# combo_-_no_usb_-_pth.net
KiCad netlist of a schematic drawn in EAGLE
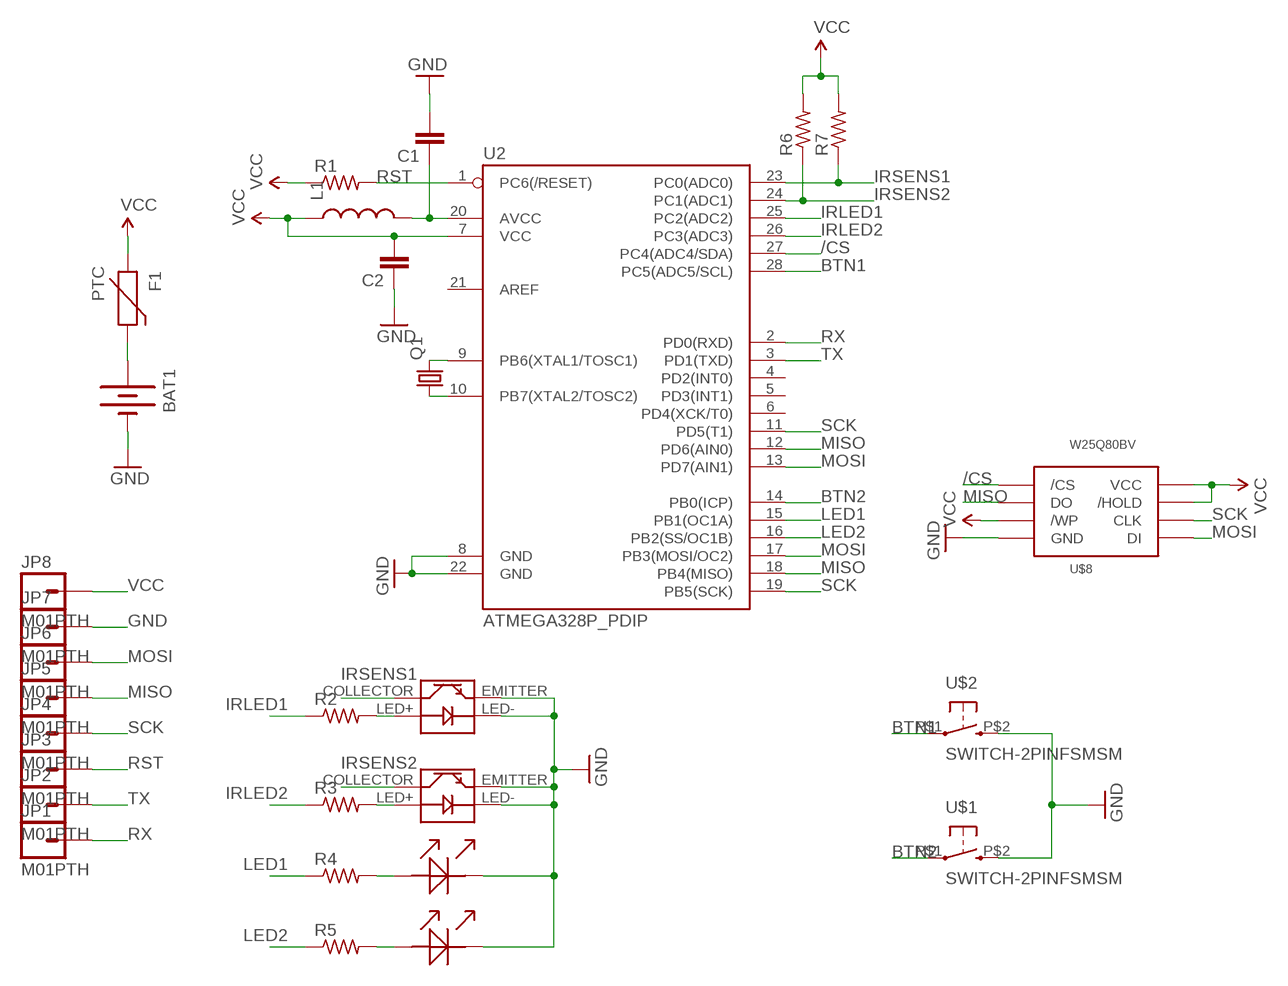
[diagram p0: schematic, sheet 1]

(export (version "E")
  (design (tool "Eeschema 10.0.6"))
  (components
    (comp (ref "BAT1")
      (value "BATTERYBA2032SM")
      (footprint "eagle-import:BA2032SM")
      (libsource (lib "eagle-import") (part "BATTERYBA2032SM"))
    )
    (comp (ref "C1")
      (value "CAP0805")
      (footprint "eagle-import:0805")
      (libsource (lib "eagle-import") (part "CAP0805"))
    )
    (comp (ref "C2")
      (value "CAP0805")
      (footprint "eagle-import:0805")
      (libsource (lib "eagle-import") (part "CAP0805"))
    )
    (comp (ref "F1")
      (value "PTC")
      (footprint "eagle-import:R0805")
      (libsource (lib "eagle-import") (part "PTC"))
    )
    (comp (ref "JP1")
      (value "M01PTH")
      (footprint "eagle-import:1X01")
      (libsource (lib "eagle-import") (part "M01PTH"))
    )
    (comp (ref "JP2")
      (value "M01PTH")
      (footprint "eagle-import:1X01")
      (libsource (lib "eagle-import") (part "M01PTH"))
    )
    (comp (ref "JP3")
      (value "M01PTH")
      (footprint "eagle-import:1X01")
      (libsource (lib "eagle-import") (part "M01PTH"))
    )
    (comp (ref "JP4")
      (value "M01PTH")
      (footprint "eagle-import:1X01")
      (libsource (lib "eagle-import") (part "M01PTH"))
    )
    (comp (ref "JP5")
      (value "M01PTH")
      (footprint "eagle-import:1X01")
      (libsource (lib "eagle-import") (part "M01PTH"))
    )
    (comp (ref "JP6")
      (value "M01PTH")
      (footprint "eagle-import:1X01")
      (libsource (lib "eagle-import") (part "M01PTH"))
    )
    (comp (ref "JP7")
      (value "M01PTH")
      (footprint "eagle-import:1X01")
      (libsource (lib "eagle-import") (part "M01PTH"))
    )
    (comp (ref "JP8")
      (value "M01PTH")
      (footprint "eagle-import:1X01")
      (libsource (lib "eagle-import") (part "M01PTH"))
    )
    (comp (ref "L1")
      (value "INDUCTOR0805")
      (footprint "eagle-import:0805")
      (libsource (lib "eagle-import") (part "INDUCTOR0805"))
    )
    (comp (ref "Q1")
      (value "CRYSTALTC26V")
      (footprint "eagle-import:TC26V")
      (libsource (lib "eagle-import") (part "CRYSTALTC26V"))
    )
    (comp (ref "R1")
      (value "R-US_M0805")
      (footprint "eagle-import:M0805")
      (libsource (lib "eagle-import") (part "R-US_M0805"))
    )
    (comp (ref "R2")
      (value "R-US_M0805")
      (footprint "eagle-import:M0805")
      (libsource (lib "eagle-import") (part "R-US_M0805"))
    )
    (comp (ref "R3")
      (value "R-US_M0805")
      (footprint "eagle-import:M0805")
      (libsource (lib "eagle-import") (part "R-US_M0805"))
    )
    (comp (ref "R4")
      (value "R-US_M0805")
      (footprint "eagle-import:M0805")
      (libsource (lib "eagle-import") (part "R-US_M0805"))
    )
    (comp (ref "R5")
      (value "R-US_M0805")
      (footprint "eagle-import:M0805")
      (libsource (lib "eagle-import") (part "R-US_M0805"))
    )
    (comp (ref "R6")
      (value "R-US_M0805")
      (footprint "eagle-import:M0805")
      (libsource (lib "eagle-import") (part "R-US_M0805"))
    )
    (comp (ref "R7")
      (value "R-US_M0805")
      (footprint "eagle-import:M0805")
      (libsource (lib "eagle-import") (part "R-US_M0805"))
    )
    (comp (ref "U$1")
      (value "SWITCH-2PINFSMSM")
      (footprint "eagle-import:FSMSM-BUTTON")
      (libsource (lib "eagle-import") (part "SWITCH-2PINFSMSM"))
    )
    (comp (ref "U$2")
      (value "SWITCH-2PINFSMSM")
      (footprint "eagle-import:FSMSM-BUTTON")
      (libsource (lib "eagle-import") (part "SWITCH-2PINFSMSM"))
    )
    (comp (ref "U$3")
      (value "IR_SENSORQRE1113")
      (footprint "eagle-import:QRE1113")
      (libsource (lib "eagle-import") (part "IR_SENSORQRE1113"))
    )
    (comp (ref "U$4")
      (value "IR_SENSORQRE1113")
      (footprint "eagle-import:QRE1113")
      (libsource (lib "eagle-import") (part "IR_SENSORQRE1113"))
    )
    (comp (ref "U$5")
      (value "LED0603")
      (footprint "eagle-import:0603")
      (libsource (lib "eagle-import") (part "LED0603"))
    )
    (comp (ref "U$6")
      (value "LED0603")
      (footprint "eagle-import:0603")
      (libsource (lib "eagle-import") (part "LED0603"))
    )
    (comp (ref "U$8")
      (value "W25Q80BVSOIC-08")
      (footprint "eagle-import:W25Q80BV-SOIC-208MIL")
      (libsource (lib "eagle-import") (part "W25Q80BVSOIC-08"))
    )
    (comp (ref "U2")
      (value "ATMEGA328P_PDIP")
      (footprint "eagle-import:DIL28-3")
      (libsource (lib "eagle-import") (part "ATMEGA328P_PDIP"))
    )
  )
  (nets
    (net (code "1") (name "/BTN1") (class "Default")
      (node (ref "U$2") (pin "P$1") (pinfunction "1_P$1") (pintype "passive"))
      (node (ref "U2") (pin "28") (pinfunction "PC5(ADC5/SCL)_28") (pintype "bidirectional"))
    )
    (net (code "2") (name "/BTN2") (class "Default")
      (node (ref "U$1") (pin "P$1") (pinfunction "1_P$1") (pintype "passive"))
      (node (ref "U2") (pin "14") (pinfunction "PB0(ICP)_14") (pintype "bidirectional"))
    )
    (net (code "3") (name "/IRLED1") (class "Default")
      (node (ref "R2") (pin "1") (pinfunction "1_1") (pintype "passive"))
      (node (ref "U2") (pin "25") (pinfunction "PC2(ADC2)_25") (pintype "bidirectional"))
    )
    (net (code "4") (name "/IRLED2") (class "Default")
      (node (ref "R3") (pin "1") (pinfunction "1_1") (pintype "passive"))
      (node (ref "U2") (pin "26") (pinfunction "PC3(ADC3)_26") (pintype "bidirectional"))
    )
    (net (code "5") (name "/IRSENS1") (class "Default")
      (node (ref "R7") (pin "1") (pinfunction "1_1") (pintype "passive"))
      (node (ref "U$3") (pin "COLLECTOR") (pinfunction "COLLECTOR_COLLECTOR") (pintype "input"))
      (node (ref "U2") (pin "23") (pinfunction "PC0(ADC0)_23") (pintype "bidirectional"))
    )
    (net (code "6") (name "/IRSENS2") (class "Default")
      (node (ref "R6") (pin "1") (pinfunction "1_1") (pintype "passive"))
      (node (ref "U$4") (pin "COLLECTOR") (pinfunction "COLLECTOR_COLLECTOR") (pintype "input"))
      (node (ref "U2") (pin "24") (pinfunction "PC1(ADC1)_24") (pintype "bidirectional"))
    )
    (net (code "7") (name "/LED1") (class "Default")
      (node (ref "R4") (pin "1") (pinfunction "1_1") (pintype "passive"))
      (node (ref "U2") (pin "15") (pinfunction "PB1(OC1A)_15") (pintype "bidirectional"))
    )
    (net (code "8") (name "/LED2") (class "Default")
      (node (ref "R5") (pin "1") (pinfunction "1_1") (pintype "passive"))
      (node (ref "U2") (pin "16") (pinfunction "PB2(SS/OC1B)_16") (pintype "bidirectional"))
    )
    (net (code "9") (name "/MISO") (class "Default")
      (node (ref "JP5") (pin "1") (pinfunction "1_1") (pintype "passive"))
      (node (ref "U$8") (pin "DO") (pinfunction "DO_DO") (pintype "bidirectional"))
      (node (ref "U2") (pin "12") (pinfunction "PD6(AIN0)_12") (pintype "bidirectional"))
      (node (ref "U2") (pin "18") (pinfunction "PB4(MISO)_18") (pintype "bidirectional"))
    )
    (net (code "10") (name "/MOSI") (class "Default")
      (node (ref "JP6") (pin "1") (pinfunction "1_1") (pintype "passive"))
      (node (ref "U$8") (pin "DI") (pinfunction "DI_DI") (pintype "bidirectional"))
      (node (ref "U2") (pin "13") (pinfunction "PD7(AIN1)_13") (pintype "bidirectional"))
      (node (ref "U2") (pin "17") (pinfunction "PB3(MOSI/OC2)_17") (pintype "bidirectional"))
    )
    (net (code "11") (name "/RST") (class "Default")
      (node (ref "JP3") (pin "1") (pinfunction "1_1") (pintype "passive"))
      (node (ref "R1") (pin "2") (pinfunction "2_2") (pintype "passive"))
      (node (ref "U2") (pin "1") (pinfunction "PC6(/RESET)_1") (pintype "bidirectional"))
    )
    (net (code "12") (name "/RX") (class "Default")
      (node (ref "JP1") (pin "1") (pinfunction "1_1") (pintype "passive"))
      (node (ref "U2") (pin "2") (pinfunction "PD0(RXD)_2") (pintype "bidirectional"))
    )
    (net (code "13") (name "/SCK") (class "Default")
      (node (ref "JP4") (pin "1") (pinfunction "1_1") (pintype "passive"))
      (node (ref "U$8") (pin "CLK") (pinfunction "CLK_CLK") (pintype "input"))
      (node (ref "U2") (pin "11") (pinfunction "PD5(T1)_11") (pintype "bidirectional"))
      (node (ref "U2") (pin "19") (pinfunction "PB5(SCK)_19") (pintype "bidirectional"))
    )
    (net (code "14") (name "/TX") (class "Default")
      (node (ref "JP2") (pin "1") (pinfunction "1_1") (pintype "passive"))
      (node (ref "U2") (pin "3") (pinfunction "PD1(TXD)_3") (pintype "bidirectional"))
    )
    (net (code "15") (name "/{slash}CS") (class "Default")
      (node (ref "U$8") (pin "/CS") (pinfunction "/CS_/CS") (pintype "input"))
      (node (ref "U2") (pin "27") (pinfunction "PC4(ADC4/SDA)_27") (pintype "bidirectional"))
    )
    (net (code "16") (name "GND") (class "Default")
      (node (ref "BAT1") (pin "-") (pinfunction "-_-") (pintype "power_in"))
      (node (ref "C1") (pin "2") (pinfunction "2_2") (pintype "passive"))
      (node (ref "C2") (pin "1") (pinfunction "1_1") (pintype "passive"))
      (node (ref "JP7") (pin "1") (pinfunction "1_1") (pintype "passive"))
      (node (ref "U$1") (pin "P$2") (pinfunction "3_P$2") (pintype "passive"))
      (node (ref "U$2") (pin "P$2") (pinfunction "3_P$2") (pintype "passive"))
      (node (ref "U$3") (pin "EMITTER") (pinfunction "EMITTER_EMITTER") (pintype "input"))
      (node (ref "U$3") (pin "LED-") (pinfunction "LED-_LED-") (pintype "input"))
      (node (ref "U$4") (pin "EMITTER") (pinfunction "EMITTER_EMITTER") (pintype "input"))
      (node (ref "U$4") (pin "LED-") (pinfunction "LED-_LED-") (pintype "input"))
      (node (ref "U$5") (pin "2") (pinfunction "-_2") (pintype "bidirectional"))
      (node (ref "U$6") (pin "2") (pinfunction "-_2") (pintype "bidirectional"))
      (node (ref "U$8") (pin "GND") (pinfunction "GND_GND") (pintype "power_in"))
      (node (ref "U2") (pin "22") (pinfunction "GND_22") (pintype "bidirectional"))
      (node (ref "U2") (pin "8") (pinfunction "GND_8") (pintype "bidirectional"))
    )
    (net (code "17") (name "Net-(BAT1-Pad+)") (class "Default")
      (node (ref "BAT1") (pin "+") (pinfunction "+_+") (pintype "power_in"))
      (node (ref "F1") (pin "2") (pinfunction "2_2") (pintype "bidirectional"))
    )
    (net (code "18") (name "Net-(R2-Pad2)") (class "Default")
      (node (ref "R2") (pin "2") (pinfunction "2_2") (pintype "passive"))
      (node (ref "U$3") (pin "LED+") (pinfunction "LED+_LED+") (pintype "input"))
    )
    (net (code "19") (name "Net-(R3-Pad2)") (class "Default")
      (node (ref "R3") (pin "2") (pinfunction "2_2") (pintype "passive"))
      (node (ref "U$4") (pin "LED+") (pinfunction "LED+_LED+") (pintype "input"))
    )
    (net (code "20") (name "Net-(U$5-+)") (class "Default")
      (node (ref "R4") (pin "2") (pinfunction "2_2") (pintype "passive"))
      (node (ref "U$5") (pin "1") (pinfunction "+_1") (pintype "bidirectional"))
    )
    (net (code "21") (name "Net-(U$6-+)") (class "Default")
      (node (ref "R5") (pin "2") (pinfunction "2_2") (pintype "passive"))
      (node (ref "U$6") (pin "1") (pinfunction "+_1") (pintype "bidirectional"))
    )
    (net (code "22") (name "Net-(U2-AVCC)") (class "Default")
      (node (ref "C1") (pin "1") (pinfunction "1_1") (pintype "passive"))
      (node (ref "L1") (pin "2") (pinfunction "2_2") (pintype "passive"))
      (node (ref "U2") (pin "20") (pinfunction "AVCC_20") (pintype "bidirectional"))
    )
    (net (code "23") (name "Net-(U2-PB6(XTAL1{slash}TOSC1))") (class "Default")
      (node (ref "Q1") (pin "2") (pinfunction "2_2") (pintype "passive"))
      (node (ref "U2") (pin "9") (pinfunction "PB6(XTAL1/TOSC1)_9") (pintype "bidirectional"))
    )
    (net (code "24") (name "Net-(U2-PB7(XTAL2{slash}TOSC2))") (class "Default")
      (node (ref "Q1") (pin "1") (pinfunction "1_1") (pintype "passive"))
      (node (ref "U2") (pin "10") (pinfunction "PB7(XTAL2/TOSC2)_10") (pintype "bidirectional"))
    )
    (net (code "25") (name "VCC") (class "Default")
      (node (ref "C2") (pin "2") (pinfunction "2_2") (pintype "passive"))
      (node (ref "F1") (pin "1") (pinfunction "1_1") (pintype "bidirectional"))
      (node (ref "JP8") (pin "1") (pinfunction "1_1") (pintype "passive"))
      (node (ref "L1") (pin "1") (pinfunction "1_1") (pintype "passive"))
      (node (ref "R1") (pin "1") (pinfunction "1_1") (pintype "passive"))
      (node (ref "R6") (pin "2") (pinfunction "2_2") (pintype "passive"))
      (node (ref "R7") (pin "2") (pinfunction "2_2") (pintype "passive"))
      (node (ref "U$8") (pin "/HOLD") (pinfunction "/HOLD_/HOLD") (pintype "bidirectional"))
      (node (ref "U$8") (pin "/WP") (pinfunction "/WP_/WP") (pintype "bidirectional"))
      (node (ref "U$8") (pin "VCC") (pinfunction "VCC_VCC") (pintype "power_in"))
      (node (ref "U2") (pin "7") (pinfunction "VCC_7") (pintype "bidirectional"))
    )
    (net (code "26") (name "unconnected-(U2-AREF-Pad21)") (class "Default")
      (node (ref "U2") (pin "21") (pinfunction "AREF_21") (pintype "bidirectional"))
    )
    (net (code "27") (name "unconnected-(U2-PD2(INT0)-Pad4)") (class "Default")
      (node (ref "U2") (pin "4") (pinfunction "PD2(INT0)_4") (pintype "bidirectional"))
    )
    (net (code "28") (name "unconnected-(U2-PD3(INT1)-Pad5)") (class "Default")
      (node (ref "U2") (pin "5") (pinfunction "PD3(INT1)_5") (pintype "bidirectional"))
    )
    (net (code "29") (name "unconnected-(U2-PD4(XCK{slash}T0)-Pad6)") (class "Default")
      (node (ref "U2") (pin "6") (pinfunction "PD4(XCK/T0)_6") (pintype "bidirectional"))
    )
  )
)
